# TPDH-Walrus_HardMount.net
KiCad netlist of a schematic drawn in EAGLE
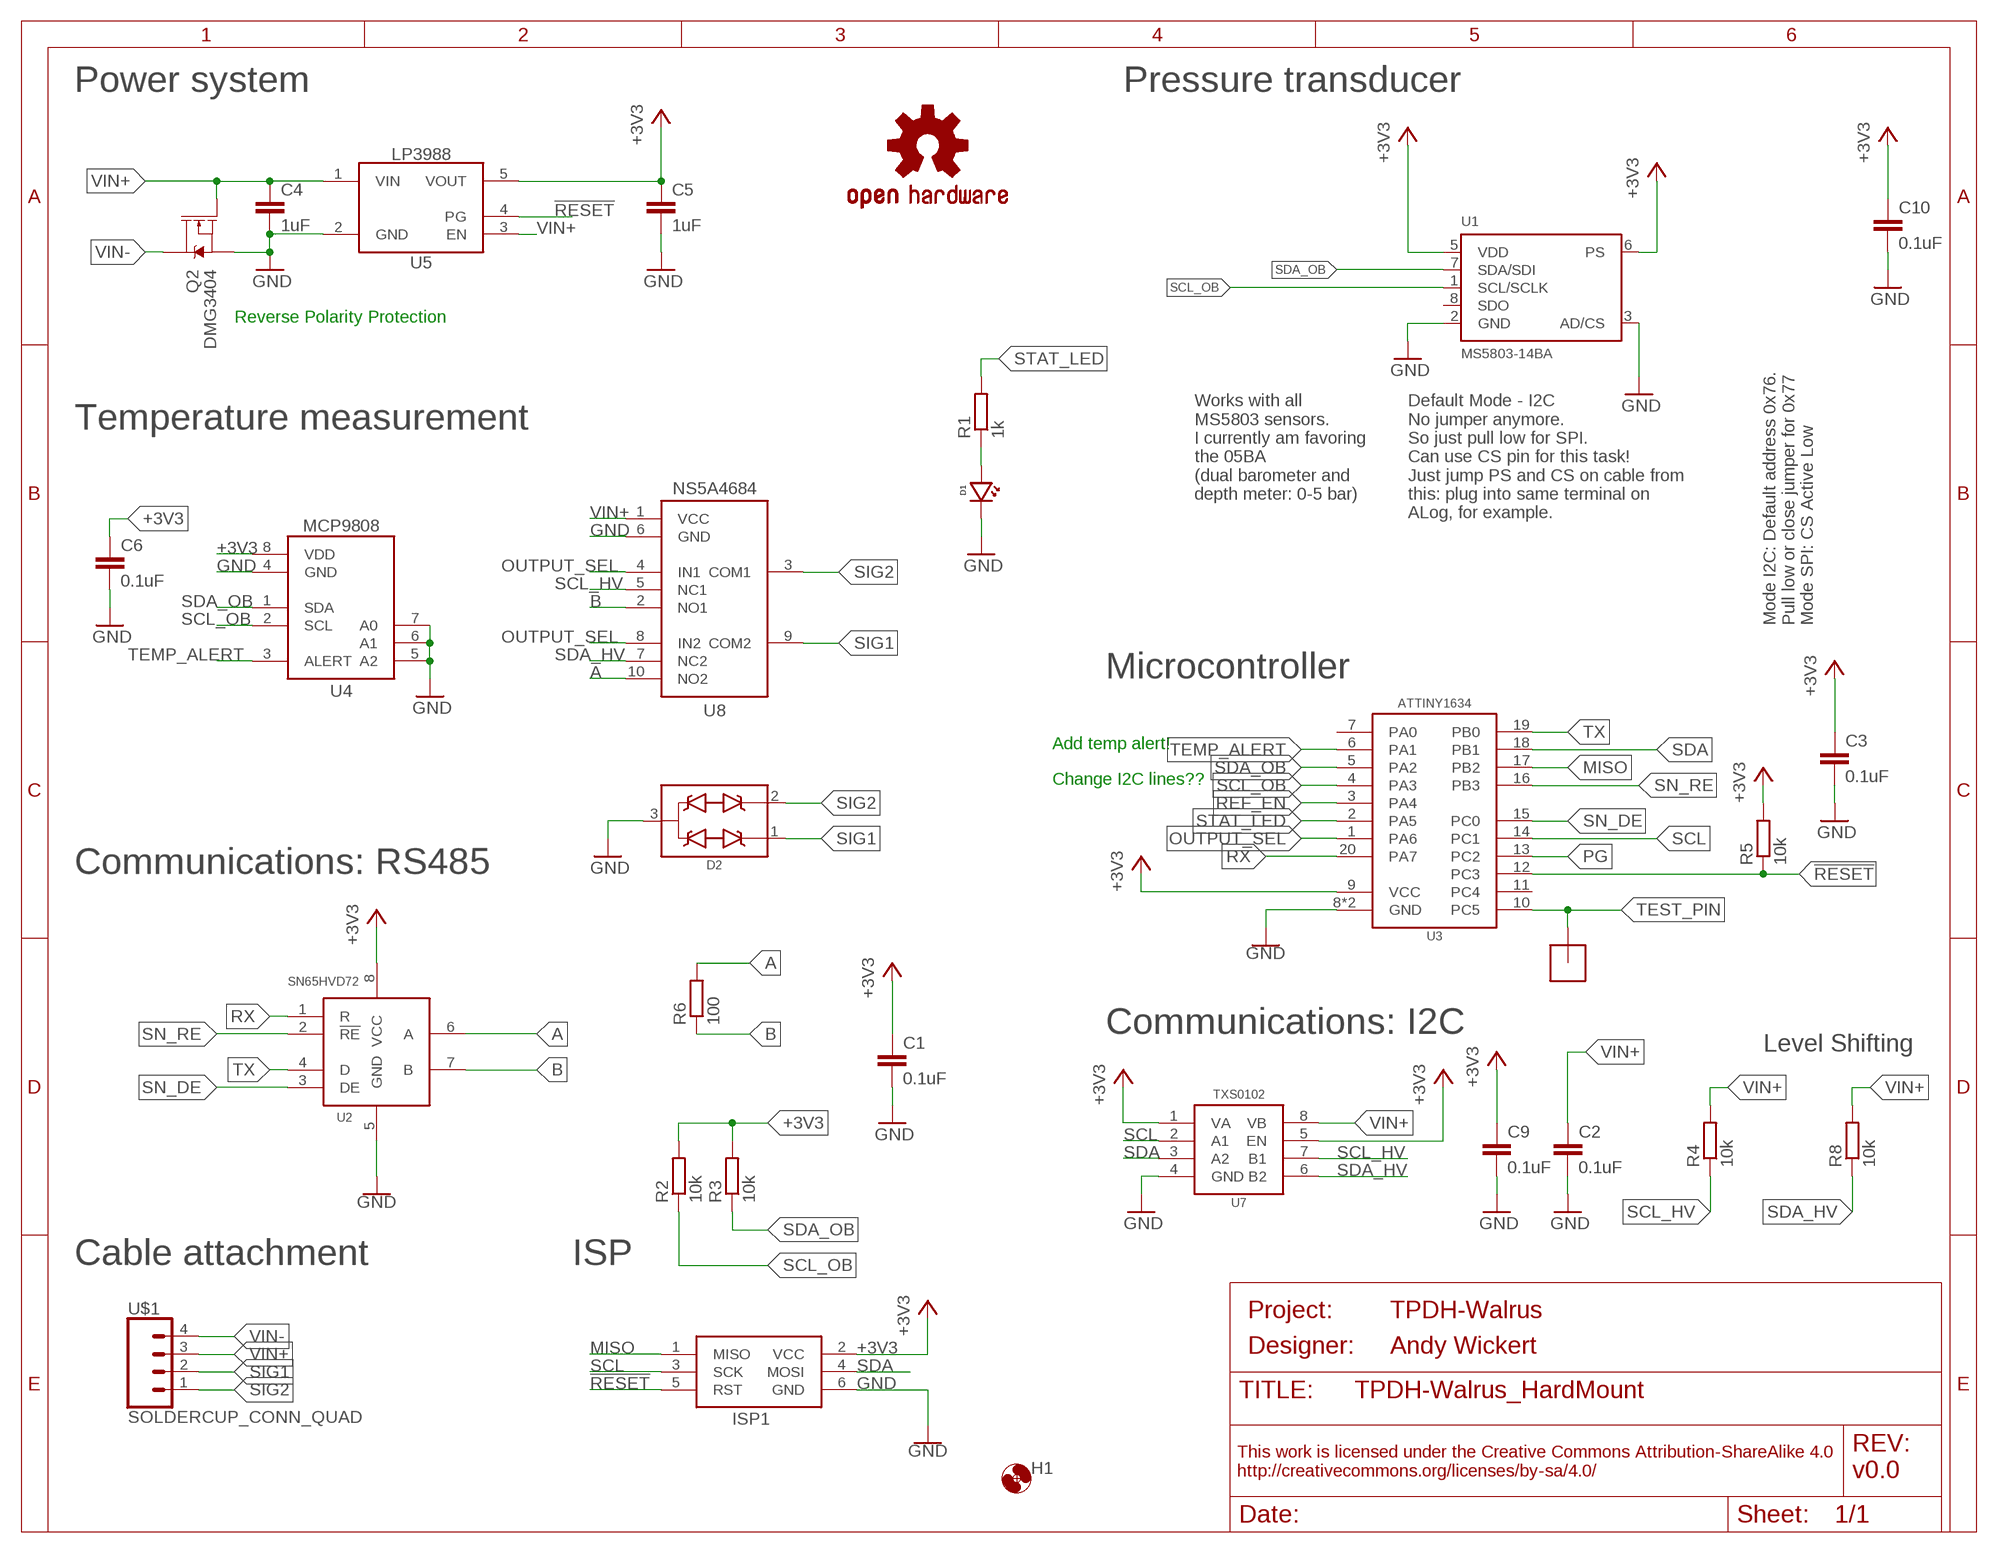
[diagram p0: schematic, sheet 1]

(export (version "E")
  (design (tool "Eeschema 10.0.6"))
  (components
    (comp (ref "C1")
      (value "0.1uF")
      (footprint "eagle-import:C0402")
      (fields (field (name "MF") "Murata") (field (name "MPN") "GCM155R71C104KA55D"))
      (libsource (lib "eagle-import") (part "C-EUC04020.1UF"))
    )
    (comp (ref "C2")
      (value "0.1uF")
      (footprint "eagle-import:C0402")
      (fields (field (name "MF") "Murata") (field (name "MPN") "GCM155R71C104KA55D"))
      (libsource (lib "eagle-import") (part "C-EUC04020.1UF"))
    )
    (comp (ref "C3")
      (value "0.1uF")
      (footprint "eagle-import:C0402")
      (fields (field (name "MF") "Murata") (field (name "MPN") "GCM155R71C104KA55D"))
      (libsource (lib "eagle-import") (part "C-EUC04020.1UF"))
    )
    (comp (ref "C4")
      (value "1uF")
      (footprint "eagle-import:C0603")
      (fields (field (name "MF") "Samsung") (field (name "MPN") "1276-6524-1-ND"))
      (libsource (lib "eagle-import") (part "C-EUC06031UF"))
    )
    (comp (ref "C5")
      (value "1uF")
      (footprint "eagle-import:C0603")
      (fields (field (name "MF") "Samsung") (field (name "MPN") "1276-6524-1-ND"))
      (libsource (lib "eagle-import") (part "C-EUC06031UF"))
    )
    (comp (ref "C6")
      (value "0.1uF")
      (footprint "eagle-import:C0402")
      (fields (field (name "MF") "Murata") (field (name "MPN") "GCM155R71C104KA55D"))
      (libsource (lib "eagle-import") (part "C-EUC04020.1UF"))
    )
    (comp (ref "C9")
      (value "0.1uF")
      (footprint "eagle-import:C0402")
      (fields (field (name "MF") "Murata") (field (name "MPN") "GCM155R71C104KA55D"))
      (libsource (lib "eagle-import") (part "C-EUC04020.1UF"))
    )
    (comp (ref "C10")
      (value "0.1uF")
      (footprint "eagle-import:C0402")
      (fields (field (name "MF") "Murata") (field (name "MPN") "GCM155R71C104KA55D"))
      (libsource (lib "eagle-import") (part "C-EUC04020.1UF"))
    )
    (comp (ref "D1")
      (value "LEDBLUE0603")
      (footprint "eagle-import:LED_0603")
      (fields (field (name "MF") "Wurth") (field (name "MPN") "150060BS75000"))
      (libsource (lib "eagle-import") (part "LED0603BLUE"))
    )
    (comp (ref "D2")
      (value "TVSSM712")
      (footprint "eagle-import:SOT23-3")
      (fields (field (name "MF") "Bourns") (field (name "MPN") "CDSOT23-SM712"))
      (libsource (lib "eagle-import") (part "TVSSM712"))
    )
    (comp (ref "H1")
      (value "MOUNTING_HOLE2_NP")
      (footprint "eagle-import:2_56")
      (libsource (lib "eagle-import") (part "MOUNTING_HOLE2_NP"))
    )
    (comp (ref "ISP1")
      (value "AVRISP-6")
      (footprint "eagle-import:AVRISP")
      (libsource (lib "eagle-import") (part "AVRISP-6"))
    )
    (comp (ref "LOGO1")
      (value "OSHW-LOGOM")
      (footprint "eagle-import:OSHW-LOGO-M")
      (libsource (lib "eagle-import") (part "OSHW-LOGOM"))
    )
    (comp (ref "Q2")
      (value "DMG3404")
      (footprint "eagle-import:SOT23-3")
      (fields (field (name "MF") "Diodes Incorporated") (field (name "MPN") "DMG3404L-7"))
      (libsource (lib "eagle-import") (part "MOSFET-NCH-DMG3404L"))
    )
    (comp (ref "R1")
      (value "1k")
      (footprint "eagle-import:R0603")
      (fields (field (name "MF") "Yageo") (field (name "MPN") "AC0603FR-071KL"))
      (libsource (lib "eagle-import") (part "R-EU_R06031K"))
    )
    (comp (ref "R2")
      (value "10k")
      (footprint "eagle-import:R0402")
      (fields (field (name "MF") "Yageo") (field (name "MPN") "RC0603FR-0710KL"))
      (libsource (lib "eagle-import") (part "R-EU_R040210K"))
    )
    (comp (ref "R3")
      (value "10k")
      (footprint "eagle-import:R0402")
      (fields (field (name "MF") "Yageo") (field (name "MPN") "RC0603FR-0710KL"))
      (libsource (lib "eagle-import") (part "R-EU_R040210K"))
    )
    (comp (ref "R4")
      (value "10k")
      (footprint "eagle-import:R0402")
      (fields (field (name "MF") "Yageo") (field (name "MPN") "RC0603FR-0710KL"))
      (libsource (lib "eagle-import") (part "R-EU_R040210K"))
    )
    (comp (ref "R5")
      (value "10k")
      (footprint "eagle-import:R0402")
      (fields (field (name "MF") "Yageo") (field (name "MPN") "RC0603FR-0710KL"))
      (libsource (lib "eagle-import") (part "R-EU_R040210K"))
    )
    (comp (ref "R6")
      (value "100")
      (footprint "eagle-import:R0402")
      (fields (field (name "MF") "Yageo") (field (name "MPN") "RC0402FR-07100RL"))
      (libsource (lib "eagle-import") (part "R-EU_R0402100"))
    )
    (comp (ref "R8")
      (value "10k")
      (footprint "eagle-import:R0402")
      (fields (field (name "MF") "Yageo") (field (name "MPN") "RC0603FR-0710KL"))
      (libsource (lib "eagle-import") (part "R-EU_R040210K"))
    )
    (comp (ref "U$1")
      (value "SOLDERCUP_CONN_QUAD")
      (footprint "eagle-import:SOLDERCUP_CONN_QUAD")
      (libsource (lib "eagle-import") (part "SOLDERCUP_CONN_QUAD"))
    )
    (comp (ref "U$12")
      (value "POGO_PAD")
      (footprint "eagle-import:POGO_PAD")
      (libsource (lib "eagle-import") (part "POGO_PAD"))
    )
    (comp (ref "U1")
      (value "MS5803-14BA")
      (footprint "eagle-import:MS5803")
      (fields (field (name "MF") "TE") (field (name "MPN") "MS580305BA01-00"))
      (libsource (lib "eagle-import") (part "MS5803-14BA"))
    )
    (comp (ref "U2")
      (value "SN65HVD72DSOIC")
      (footprint "eagle-import:SO08")
      (fields (field (name "DISP") "SN65HVD72") (field (name "MF") "TI") (field (name "MPN") "SN65HVD72DR"))
      (libsource (lib "eagle-import") (part "SN65HVD72SOICD"))
    )
    (comp (ref "U3")
      (value "ATTINY1634QFN")
      (footprint "eagle-import:QFN20")
      (fields (field (name "MF") "Atmel") (field (name "MPN") "ATTINY1634-MUR"))
      (libsource (lib "eagle-import") (part "ATTINY1634QFN"))
    )
    (comp (ref "U4")
      (value "MCP9808MSOP")
      (footprint "eagle-import:MSOP_8")
      (fields (field (name "MF") "Microchip") (field (name "MPN") "MCP9808T-E/MS"))
      (libsource (lib "eagle-import") (part "MCP9808MSOP"))
    )
    (comp (ref "U5")
      (value "LP39883.3VDBV")
      (footprint "eagle-import:DBV0005A")
      (fields (field (name "MF") "TI") (field (name "MPN") "LP3988IMF-3.3/NOPB"))
      (libsource (lib "eagle-import") (part "LP3988DBV3.3V"))
    )
    (comp (ref "U7")
      (value "TXS0102DQM")
      (footprint "eagle-import:DQM_R-PX2SON-N8")
      (fields (field (name "MF") "TI") (field (name "MPN") "TXS0102DQMR"))
      (libsource (lib "eagle-import") (part "TXS0102DQM"))
    )
    (comp (ref "U8")
      (value "NS5A4684S")
      (footprint "eagle-import:WQFN10")
      (fields
        (field (name "DISP") "NS5A4684")
        (field (name "MF") "ON Semiconductor")
        (field (name "MPN") "NS5A4684SMNTAG")
      )
      (libsource (lib "eagle-import") (part "NS5A4684S"))
    )
  )
  (nets
    (net (code "1") (name "+3V3") (class "Default")
      (node (ref "C1") (pin "1") (pinfunction "1_1") (pintype "passive"))
      (node (ref "C10") (pin "1") (pinfunction "1_1") (pintype "passive"))
      (node (ref "C3") (pin "1") (pinfunction "1_1") (pintype "passive"))
      (node (ref "C5") (pin "1") (pinfunction "1_1") (pintype "passive"))
      (node (ref "C6") (pin "1") (pinfunction "1_1") (pintype "passive"))
      (node (ref "C9") (pin "1") (pinfunction "1_1") (pintype "passive"))
      (node (ref "ISP1") (pin "2") (pinfunction "VCC_2") (pintype "power_in"))
      (node (ref "R2") (pin "2") (pinfunction "2_2") (pintype "passive"))
      (node (ref "R3") (pin "2") (pinfunction "2_2") (pintype "passive"))
      (node (ref "R5") (pin "2") (pinfunction "2_2") (pintype "passive"))
      (node (ref "U1") (pin "5") (pinfunction "VDD_5") (pintype "bidirectional"))
      (node (ref "U1") (pin "6") (pinfunction "PS_6") (pintype "bidirectional"))
      (node (ref "U2") (pin "8") (pinfunction "VCC_8") (pintype "power_in"))
      (node (ref "U3") (pin "9") (pinfunction "VCC_9") (pintype "power_in"))
      (node (ref "U4") (pin "8") (pinfunction "VDD_8") (pintype "power_in"))
      (node (ref "U5") (pin "5") (pinfunction "VOUT_5") (pintype "power_in"))
      (node (ref "U7") (pin "1") (pinfunction "VA_1") (pintype "power_in"))
      (node (ref "U7") (pin "5") (pinfunction "EN_5") (pintype "input"))
    )
    (net (code "2") (name "/~{RESET}") (class "Default")
      (node (ref "ISP1") (pin "5") (pinfunction "RST_5") (pintype "output"))
      (node (ref "R5") (pin "1") (pinfunction "1_1") (pintype "passive"))
      (node (ref "U3") (pin "12") (pinfunction "PC3_12") (pintype "bidirectional"))
      (node (ref "U5") (pin "4") (pinfunction "PG_4") (pintype "output"))
    )
    (net (code "3") (name "A") (class "Default")
      (node (ref "R6") (pin "2") (pinfunction "2_2") (pintype "passive"))
      (node (ref "U2") (pin "6") (pinfunction "A_6") (pintype "bidirectional"))
      (node (ref "U8") (pin "10") (pinfunction "NO2_10") (pintype "bidirectional"))
    )
    (net (code "4") (name "B") (class "Default")
      (node (ref "R6") (pin "1") (pinfunction "1_1") (pintype "passive"))
      (node (ref "U2") (pin "7") (pinfunction "B_7") (pintype "bidirectional"))
      (node (ref "U8") (pin "2") (pinfunction "NO1_2") (pintype "bidirectional"))
    )
    (net (code "5") (name "GND") (class "Default")
      (node (ref "C1") (pin "2") (pinfunction "2_2") (pintype "passive"))
      (node (ref "C10") (pin "2") (pinfunction "2_2") (pintype "passive"))
      (node (ref "C2") (pin "2") (pinfunction "2_2") (pintype "passive"))
      (node (ref "C3") (pin "2") (pinfunction "2_2") (pintype "passive"))
      (node (ref "C4") (pin "2") (pinfunction "2_2") (pintype "passive"))
      (node (ref "C5") (pin "2") (pinfunction "2_2") (pintype "passive"))
      (node (ref "C6") (pin "2") (pinfunction "2_2") (pintype "passive"))
      (node (ref "C9") (pin "2") (pinfunction "2_2") (pintype "passive"))
      (node (ref "D1") (pin "CATHODE") (pinfunction "CATHODE_CATHODE") (pintype "power_in"))
      (node (ref "D2") (pin "3") (pinfunction "COM_3") (pintype "input"))
      (node (ref "ISP1") (pin "6") (pinfunction "GND_6") (pintype "power_in"))
      (node (ref "Q2") (pin "2") (pinfunction "S_2") (pintype "bidirectional"))
      (node (ref "U1") (pin "2") (pinfunction "GND_2") (pintype "bidirectional"))
      (node (ref "U1") (pin "3") (pinfunction "AD/CS_3") (pintype "bidirectional"))
      (node (ref "U2") (pin "5") (pinfunction "GND_5") (pintype "power_in"))
      (node (ref "U3") (pin "8") (pinfunction "GND_8") (pintype "power_in"))
      (node (ref "U3") (pin "EP") (pinfunction "GND_EP") (pintype "power_in"))
      (node (ref "U4") (pin "4") (pinfunction "GND_4") (pintype "power_in"))
      (node (ref "U4") (pin "5") (pinfunction "A2_5") (pintype "input"))
      (node (ref "U4") (pin "6") (pinfunction "A1_6") (pintype "input"))
      (node (ref "U4") (pin "7") (pinfunction "A0_7") (pintype "input"))
      (node (ref "U5") (pin "2") (pinfunction "GND_2") (pintype "power_in"))
      (node (ref "U7") (pin "4") (pinfunction "GND_4") (pintype "power_in"))
      (node (ref "U8") (pin "6") (pinfunction "GND_6") (pintype "power_in"))
    )
    (net (code "6") (name "MISO") (class "Default")
      (node (ref "ISP1") (pin "1") (pinfunction "MISO_1") (pintype "input"))
      (node (ref "U3") (pin "17") (pinfunction "PB2_17") (pintype "bidirectional"))
    )
    (net (code "7") (name "Net-(D1-PadANODE)") (class "Default")
      (node (ref "D1") (pin "ANODE") (pinfunction "ANODE_ANODE") (pintype "power_in"))
      (node (ref "R1") (pin "1") (pinfunction "1_1") (pintype "passive"))
    )
    (net (code "8") (name "OUTPUT_SEL") (class "Default")
      (node (ref "U3") (pin "1") (pinfunction "PA6_1") (pintype "bidirectional"))
      (node (ref "U8") (pin "4") (pinfunction "IN1_4") (pintype "input"))
      (node (ref "U8") (pin "8") (pinfunction "IN2_8") (pintype "input"))
    )
    (net (code "9") (name "PG") (class "Default")
      (node (ref "U3") (pin "13") (pinfunction "PC2_13") (pintype "bidirectional"))
    )
    (net (code "10") (name "REF_EN") (class "Default")
      (node (ref "U3") (pin "3") (pinfunction "PA4_3") (pintype "bidirectional"))
    )
    (net (code "11") (name "RX") (class "Default")
      (node (ref "U2") (pin "1") (pinfunction "R_1") (pintype "output"))
      (node (ref "U3") (pin "20") (pinfunction "PA7_20") (pintype "bidirectional"))
    )
    (net (code "12") (name "SCL") (class "Default")
      (node (ref "ISP1") (pin "3") (pinfunction "SCK_3") (pintype "output"))
      (node (ref "U3") (pin "14") (pinfunction "PC1_14") (pintype "bidirectional"))
      (node (ref "U7") (pin "2") (pinfunction "A1_2") (pintype "bidirectional"))
    )
    (net (code "13") (name "SCL_HV") (class "Default")
      (node (ref "R4") (pin "1") (pinfunction "1_1") (pintype "passive"))
      (node (ref "U7") (pin "7") (pinfunction "B1_7") (pintype "bidirectional"))
      (node (ref "U8") (pin "5") (pinfunction "NC1_5") (pintype "bidirectional"))
    )
    (net (code "14") (name "SCL_OB") (class "Default")
      (node (ref "R2") (pin "1") (pinfunction "1_1") (pintype "passive"))
      (node (ref "U1") (pin "1") (pinfunction "SCL/SCLK_1") (pintype "bidirectional"))
      (node (ref "U3") (pin "4") (pinfunction "PA3_4") (pintype "bidirectional"))
      (node (ref "U4") (pin "2") (pinfunction "SCL_2") (pintype "input"))
    )
    (net (code "15") (name "SDA") (class "Default")
      (node (ref "ISP1") (pin "4") (pinfunction "MOSI_4") (pintype "output"))
      (node (ref "U3") (pin "18") (pinfunction "PB1_18") (pintype "bidirectional"))
      (node (ref "U7") (pin "3") (pinfunction "A2_3") (pintype "bidirectional"))
    )
    (net (code "16") (name "SDA_HV") (class "Default")
      (node (ref "R8") (pin "1") (pinfunction "1_1") (pintype "passive"))
      (node (ref "U7") (pin "6") (pinfunction "B2_6") (pintype "bidirectional"))
      (node (ref "U8") (pin "7") (pinfunction "NC2_7") (pintype "bidirectional"))
    )
    (net (code "17") (name "SDA_OB") (class "Default")
      (node (ref "R3") (pin "1") (pinfunction "1_1") (pintype "passive"))
      (node (ref "U1") (pin "7") (pinfunction "SDA/SDI_7") (pintype "bidirectional"))
      (node (ref "U3") (pin "5") (pinfunction "PA2_5") (pintype "bidirectional"))
      (node (ref "U4") (pin "1") (pinfunction "SDA_1") (pintype "bidirectional"))
    )
    (net (code "18") (name "SIG1") (class "Default")
      (node (ref "D2") (pin "1") (pinfunction "D1_1") (pintype "input"))
      (node (ref "U$1") (pin "2") (pinfunction "2_2") (pintype "passive"))
      (node (ref "U8") (pin "9") (pinfunction "COM2_9") (pintype "bidirectional"))
    )
    (net (code "19") (name "SIG2") (class "Default")
      (node (ref "D2") (pin "2") (pinfunction "D2_2") (pintype "input"))
      (node (ref "U$1") (pin "1") (pinfunction "1_1") (pintype "passive"))
      (node (ref "U8") (pin "3") (pinfunction "COM1_3") (pintype "bidirectional"))
    )
    (net (code "20") (name "SN_DE") (class "Default")
      (node (ref "U2") (pin "3") (pinfunction "DE_3") (pintype "input"))
      (node (ref "U3") (pin "15") (pinfunction "PC0_15") (pintype "bidirectional"))
    )
    (net (code "21") (name "SN_RE") (class "Default")
      (node (ref "U2") (pin "2") (pinfunction "~{RE}_2") (pintype "input"))
      (node (ref "U3") (pin "16") (pinfunction "PB3_16") (pintype "bidirectional"))
    )
    (net (code "22") (name "STAT_LED") (class "Default")
      (node (ref "R1") (pin "2") (pinfunction "2_2") (pintype "passive"))
      (node (ref "U3") (pin "2") (pinfunction "PA5_2") (pintype "bidirectional"))
    )
    (net (code "23") (name "TEMP_ALERT") (class "Default")
      (node (ref "U3") (pin "6") (pinfunction "PA1_6") (pintype "bidirectional"))
      (node (ref "U4") (pin "3") (pinfunction "ALERT_3") (pintype "output"))
    )
    (net (code "24") (name "TEST_PIN") (class "Default")
      (node (ref "U$12") (pin "P$1") (pinfunction "P$1_P$1") (pintype "bidirectional"))
      (node (ref "U3") (pin "10") (pinfunction "PC5_10") (pintype "bidirectional"))
    )
    (net (code "25") (name "TX") (class "Default")
      (node (ref "U2") (pin "4") (pinfunction "D_4") (pintype "input"))
      (node (ref "U3") (pin "19") (pinfunction "PB0_19") (pintype "bidirectional"))
    )
    (net (code "26") (name "VIN+") (class "Default")
      (node (ref "C2") (pin "1") (pinfunction "1_1") (pintype "passive"))
      (node (ref "C4") (pin "1") (pinfunction "1_1") (pintype "passive"))
      (node (ref "Q2") (pin "1") (pinfunction "G_1") (pintype "bidirectional"))
      (node (ref "R4") (pin "2") (pinfunction "2_2") (pintype "passive"))
      (node (ref "R8") (pin "2") (pinfunction "2_2") (pintype "passive"))
      (node (ref "U$1") (pin "3") (pinfunction "3_3") (pintype "passive"))
      (node (ref "U5") (pin "1") (pinfunction "VIN_1") (pintype "power_in"))
      (node (ref "U5") (pin "3") (pinfunction "EN_3") (pintype "input"))
      (node (ref "U7") (pin "8") (pinfunction "VB_8") (pintype "power_in"))
      (node (ref "U8") (pin "1") (pinfunction "VCC_1") (pintype "power_in"))
    )
    (net (code "27") (name "VIN-") (class "Default")
      (node (ref "Q2") (pin "3") (pinfunction "D_3") (pintype "bidirectional"))
      (node (ref "U$1") (pin "4") (pinfunction "4_4") (pintype "passive"))
    )
    (net (code "28") (name "unconnected-(U1-SDO-Pad8)") (class "Default")
      (node (ref "U1") (pin "8") (pinfunction "SDO_8") (pintype "bidirectional"))
    )
    (net (code "29") (name "unconnected-(U3-PA0-Pad7)") (class "Default")
      (node (ref "U3") (pin "7") (pinfunction "PA0_7") (pintype "bidirectional"))
    )
    (net (code "30") (name "unconnected-(U3-PC4-Pad11)") (class "Default")
      (node (ref "U3") (pin "11") (pinfunction "PC4_11") (pintype "bidirectional"))
    )
  )
)
